# design.net
KiCad netlist of a schematic drawn in EAGLE
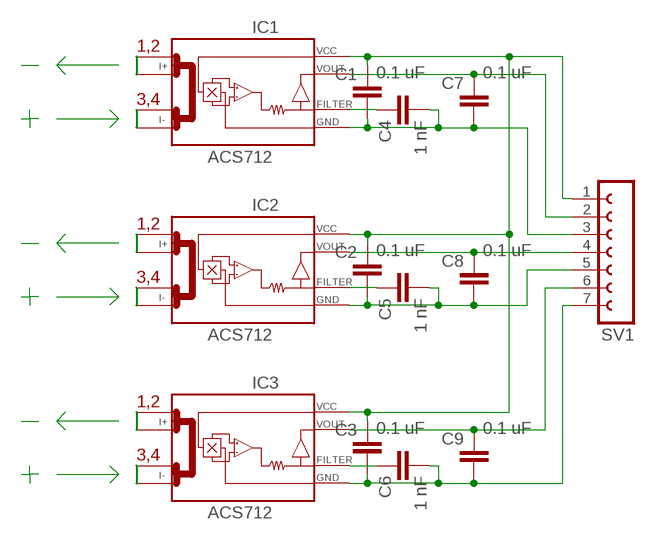
[diagram p0: schematic, sheet 1]

(export (version "E")
  (design (tool "Eeschema 10.0.6"))
  (components
    (comp (ref "C1")
      (value "C-EU025-024X044")
      (footprint "eagle-import:C025-024X044")
      (libsource (lib "eagle-import") (part "C-EU025-024X044"))
    )
    (comp (ref "C2")
      (value "C-EU025-024X044")
      (footprint "eagle-import:C025-024X044")
      (libsource (lib "eagle-import") (part "C-EU025-024X044"))
    )
    (comp (ref "C3")
      (value "C-EU025-024X044")
      (footprint "eagle-import:C025-024X044")
      (libsource (lib "eagle-import") (part "C-EU025-024X044"))
    )
    (comp (ref "C4")
      (value "1 nF")
      (footprint "eagle-import:C025-024X044")
      (libsource (lib "eagle-import") (part "C-EU025-024X044"))
    )
    (comp (ref "C5")
      (value "1 nF")
      (footprint "eagle-import:C025-024X044")
      (libsource (lib "eagle-import") (part "C-EU025-024X044"))
    )
    (comp (ref "C6")
      (value "1 nF")
      (footprint "eagle-import:C025-024X044")
      (libsource (lib "eagle-import") (part "C-EU025-024X044"))
    )
    (comp (ref "C7")
      (value "C-EU025-024X044")
      (footprint "eagle-import:C025-024X044")
      (libsource (lib "eagle-import") (part "C-EU025-024X044"))
    )
    (comp (ref "C8")
      (value "C-EU025-024X044")
      (footprint "eagle-import:C025-024X044")
      (libsource (lib "eagle-import") (part "C-EU025-024X044"))
    )
    (comp (ref "C9")
      (value "C-EU025-024X044")
      (footprint "eagle-import:C025-024X044")
      (libsource (lib "eagle-import") (part "C-EU025-024X044"))
    )
    (comp (ref "IC1")
      (value "ACS712")
      (footprint "eagle-import:SO08")
      (libsource (lib "eagle-import") (part "ACS712"))
    )
    (comp (ref "IC2")
      (value "ACS712")
      (footprint "eagle-import:SO08")
      (libsource (lib "eagle-import") (part "ACS712"))
    )
    (comp (ref "IC3")
      (value "ACS712")
      (footprint "eagle-import:SO08")
      (libsource (lib "eagle-import") (part "ACS712"))
    )
    (comp (ref "SV1")
      (value "FE07-1")
      (footprint "eagle-import:FE07")
      (libsource (lib "eagle-import") (part "FE07-1"))
    )
  )
  (nets
    (net (code "1") (name "Net-(IC1-FILTER)") (class "Default")
      (node (ref "C4") (pin "1") (pinfunction "1_1") (pintype "passive"))
      (node (ref "IC1") (pin "6") (pinfunction "FILTER_6") (pintype "bidirectional"))
    )
    (net (code "2") (name "Net-(IC1-GND)") (class "Default")
      (node (ref "C1") (pin "2") (pinfunction "2_2") (pintype "passive"))
      (node (ref "C4") (pin "2") (pinfunction "2_2") (pintype "passive"))
      (node (ref "C7") (pin "2") (pinfunction "2_2") (pintype "passive"))
      (node (ref "IC1") (pin "5") (pinfunction "GND_5") (pintype "power_in"))
      (node (ref "SV1") (pin "3") (pinfunction "3_3") (pintype "passive"))
    )
    (net (code "3") (name "Net-(IC1-VCC)") (class "Default")
      (node (ref "C1") (pin "1") (pinfunction "1_1") (pintype "passive"))
      (node (ref "C2") (pin "1") (pinfunction "1_1") (pintype "passive"))
      (node (ref "C3") (pin "1") (pinfunction "1_1") (pintype "passive"))
      (node (ref "IC1") (pin "8") (pinfunction "VCC_8") (pintype "power_in"))
      (node (ref "IC2") (pin "8") (pinfunction "VCC_8") (pintype "power_in"))
      (node (ref "IC3") (pin "8") (pinfunction "VCC_8") (pintype "power_in"))
      (node (ref "SV1") (pin "1") (pinfunction "1_1") (pintype "passive"))
    )
    (net (code "4") (name "Net-(IC1-VOUT)") (class "Default")
      (node (ref "C7") (pin "1") (pinfunction "1_1") (pintype "passive"))
      (node (ref "IC1") (pin "7") (pinfunction "VOUT_7") (pintype "output"))
      (node (ref "SV1") (pin "2") (pinfunction "2_2") (pintype "passive"))
    )
    (net (code "5") (name "Net-(IC2-FILTER)") (class "Default")
      (node (ref "C5") (pin "1") (pinfunction "1_1") (pintype "passive"))
      (node (ref "IC2") (pin "6") (pinfunction "FILTER_6") (pintype "bidirectional"))
    )
    (net (code "6") (name "Net-(IC2-GND)") (class "Default")
      (node (ref "C2") (pin "2") (pinfunction "2_2") (pintype "passive"))
      (node (ref "C5") (pin "2") (pinfunction "2_2") (pintype "passive"))
      (node (ref "C8") (pin "2") (pinfunction "2_2") (pintype "passive"))
      (node (ref "IC2") (pin "5") (pinfunction "GND_5") (pintype "power_in"))
      (node (ref "SV1") (pin "5") (pinfunction "5_5") (pintype "passive"))
    )
    (net (code "7") (name "Net-(IC2-VOUT)") (class "Default")
      (node (ref "C8") (pin "1") (pinfunction "1_1") (pintype "passive"))
      (node (ref "IC2") (pin "7") (pinfunction "VOUT_7") (pintype "output"))
      (node (ref "SV1") (pin "4") (pinfunction "4_4") (pintype "passive"))
    )
    (net (code "8") (name "Net-(IC3-FILTER)") (class "Default")
      (node (ref "C6") (pin "1") (pinfunction "1_1") (pintype "passive"))
      (node (ref "IC3") (pin "6") (pinfunction "FILTER_6") (pintype "bidirectional"))
    )
    (net (code "9") (name "Net-(IC3-GND)") (class "Default")
      (node (ref "C3") (pin "2") (pinfunction "2_2") (pintype "passive"))
      (node (ref "C6") (pin "2") (pinfunction "2_2") (pintype "passive"))
      (node (ref "C9") (pin "2") (pinfunction "2_2") (pintype "passive"))
      (node (ref "IC3") (pin "5") (pinfunction "GND_5") (pintype "power_in"))
      (node (ref "SV1") (pin "7") (pinfunction "7_7") (pintype "passive"))
    )
    (net (code "10") (name "Net-(IC3-VOUT)") (class "Default")
      (node (ref "C9") (pin "1") (pinfunction "1_1") (pintype "passive"))
      (node (ref "IC3") (pin "7") (pinfunction "VOUT_7") (pintype "output"))
      (node (ref "SV1") (pin "6") (pinfunction "6_6") (pintype "passive"))
    )
    (net (code "11") (name "unconnected-(IC1-I+_0-Pad1)") (class "Default")
      (node (ref "IC1") (pin "1") (pinfunction "I+_0_1") (pintype "bidirectional"))
    )
    (net (code "12") (name "unconnected-(IC1-I+_1-Pad2)") (class "Default")
      (node (ref "IC1") (pin "2") (pinfunction "I+_1_2") (pintype "bidirectional"))
    )
    (net (code "13") (name "unconnected-(IC1-I-_0-Pad3)") (class "Default")
      (node (ref "IC1") (pin "3") (pinfunction "I-_0_3") (pintype "bidirectional"))
    )
    (net (code "14") (name "unconnected-(IC1-I-_1-Pad4)") (class "Default")
      (node (ref "IC1") (pin "4") (pinfunction "I-_1_4") (pintype "bidirectional"))
    )
    (net (code "15") (name "unconnected-(IC2-I+_0-Pad1)") (class "Default")
      (node (ref "IC2") (pin "1") (pinfunction "I+_0_1") (pintype "bidirectional"))
    )
    (net (code "16") (name "unconnected-(IC2-I+_1-Pad2)") (class "Default")
      (node (ref "IC2") (pin "2") (pinfunction "I+_1_2") (pintype "bidirectional"))
    )
    (net (code "17") (name "unconnected-(IC2-I-_0-Pad3)") (class "Default")
      (node (ref "IC2") (pin "3") (pinfunction "I-_0_3") (pintype "bidirectional"))
    )
    (net (code "18") (name "unconnected-(IC2-I-_1-Pad4)") (class "Default")
      (node (ref "IC2") (pin "4") (pinfunction "I-_1_4") (pintype "bidirectional"))
    )
    (net (code "19") (name "unconnected-(IC3-I+_0-Pad1)") (class "Default")
      (node (ref "IC3") (pin "1") (pinfunction "I+_0_1") (pintype "bidirectional"))
    )
    (net (code "20") (name "unconnected-(IC3-I+_1-Pad2)") (class "Default")
      (node (ref "IC3") (pin "2") (pinfunction "I+_1_2") (pintype "bidirectional"))
    )
    (net (code "21") (name "unconnected-(IC3-I-_0-Pad3)") (class "Default")
      (node (ref "IC3") (pin "3") (pinfunction "I-_0_3") (pintype "bidirectional"))
    )
    (net (code "22") (name "unconnected-(IC3-I-_1-Pad4)") (class "Default")
      (node (ref "IC3") (pin "4") (pinfunction "I-_1_4") (pintype "bidirectional"))
    )
  )
)
